# io-board.net
KiCad netlist of a schematic drawn in EAGLE
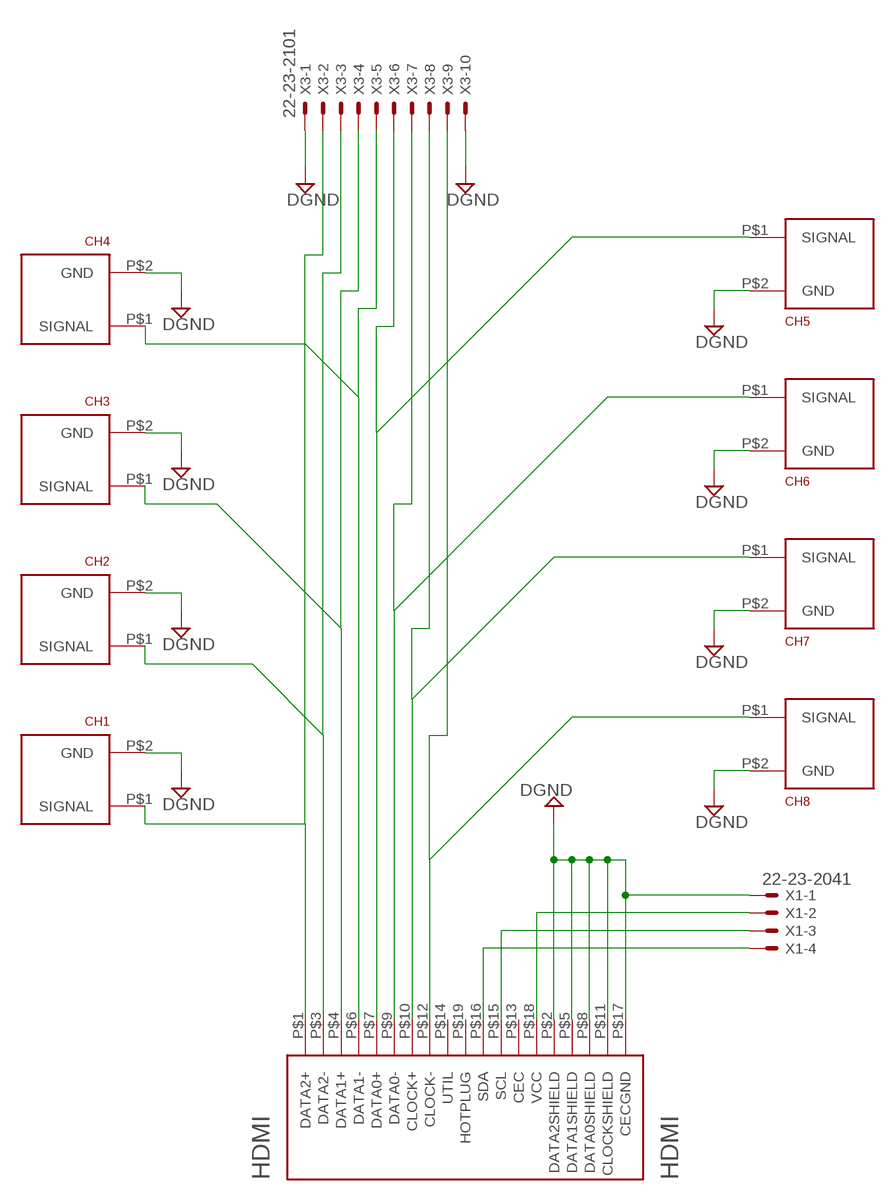
[diagram p0: schematic, sheet 1]

(export (version "E")
  (design (tool "Eeschema 10.0.6"))
  (components
    (comp (ref "CH1")
      (value "BNC_VERTICAL")
      (footprint "eagle-import:BNC_VERTICAL")
      (libsource (lib "eagle-import") (part "BNC_VERTICAL"))
    )
    (comp (ref "CH2")
      (value "BNC_VERTICAL")
      (footprint "eagle-import:BNC_VERTICAL")
      (libsource (lib "eagle-import") (part "BNC_VERTICAL"))
    )
    (comp (ref "CH3")
      (value "BNC_VERTICAL")
      (footprint "eagle-import:BNC_VERTICAL")
      (libsource (lib "eagle-import") (part "BNC_VERTICAL"))
    )
    (comp (ref "CH4")
      (value "BNC_VERTICAL")
      (footprint "eagle-import:BNC_VERTICAL")
      (libsource (lib "eagle-import") (part "BNC_VERTICAL"))
    )
    (comp (ref "CH5")
      (value "BNC_VERTICAL")
      (footprint "eagle-import:BNC_VERTICAL")
      (libsource (lib "eagle-import") (part "BNC_VERTICAL"))
    )
    (comp (ref "CH6")
      (value "BNC_VERTICAL")
      (footprint "eagle-import:BNC_VERTICAL")
      (libsource (lib "eagle-import") (part "BNC_VERTICAL"))
    )
    (comp (ref "CH7")
      (value "BNC_VERTICAL")
      (footprint "eagle-import:BNC_VERTICAL")
      (libsource (lib "eagle-import") (part "BNC_VERTICAL"))
    )
    (comp (ref "CH8")
      (value "BNC_VERTICAL")
      (footprint "eagle-import:BNC_VERTICAL")
      (libsource (lib "eagle-import") (part "BNC_VERTICAL"))
    )
    (comp (ref "HDMI")
      (value "HDMI")
      (footprint "eagle-import:HDMI_A")
      (libsource (lib "eagle-import") (part "HDMI"))
    )
    (comp (ref "X1")
      (value "22-23-2041")
      (footprint "eagle-import:22-23-2041")
      (fields (field (name "MF") "MOLEX"))
      (libsource (lib "eagle-import") (part "22-23-2041"))
    )
    (comp (ref "X3")
      (value "22-23-2101")
      (footprint "eagle-import:22-23-2101")
      (fields (field (name "MF") "MOLEX"))
      (libsource (lib "eagle-import") (part "22-23-2101"))
    )
  )
  (nets
    (net (code "1") (name "DGND") (class "Default")
      (node (ref "CH1") (pin "P$2") (pinfunction "GND_P$2") (pintype "bidirectional"))
      (node (ref "CH2") (pin "P$2") (pinfunction "GND_P$2") (pintype "bidirectional"))
      (node (ref "CH3") (pin "P$2") (pinfunction "GND_P$2") (pintype "bidirectional"))
      (node (ref "CH4") (pin "P$2") (pinfunction "GND_P$2") (pintype "bidirectional"))
      (node (ref "CH5") (pin "P$2") (pinfunction "GND_P$2") (pintype "bidirectional"))
      (node (ref "CH6") (pin "P$2") (pinfunction "GND_P$2") (pintype "bidirectional"))
      (node (ref "CH7") (pin "P$2") (pinfunction "GND_P$2") (pintype "bidirectional"))
      (node (ref "CH8") (pin "P$2") (pinfunction "GND_P$2") (pintype "bidirectional"))
      (node (ref "HDMI") (pin "P$11") (pinfunction "CLOCKSHIELD_P$11") (pintype "bidirectional"))
      (node (ref "HDMI") (pin "P$17") (pinfunction "CECGND_P$17") (pintype "bidirectional"))
      (node (ref "HDMI") (pin "P$2") (pinfunction "DATA2SHIELD_P$2") (pintype "bidirectional"))
      (node (ref "HDMI") (pin "P$5") (pinfunction "DATA1SHIELD_P$5") (pintype "bidirectional"))
      (node (ref "HDMI") (pin "P$8") (pinfunction "DATA0SHIELD_P$8") (pintype "bidirectional"))
      (node (ref "X1") (pin "1") (pinfunction "S_1") (pintype "passive"))
      (node (ref "X3") (pin "1") (pinfunction "S_1") (pintype "passive"))
      (node (ref "X3") (pin "10") (pinfunction "S_10") (pintype "passive"))
    )
    (net (code "2") (name "Net-(CH1-SIGNAL)") (class "Default")
      (node (ref "CH1") (pin "P$1") (pinfunction "SIGNAL_P$1") (pintype "bidirectional"))
      (node (ref "HDMI") (pin "P$1") (pinfunction "DATA2+_P$1") (pintype "bidirectional"))
      (node (ref "X3") (pin "2") (pinfunction "S_2") (pintype "passive"))
    )
    (net (code "3") (name "Net-(CH2-SIGNAL)") (class "Default")
      (node (ref "CH2") (pin "P$1") (pinfunction "SIGNAL_P$1") (pintype "bidirectional"))
      (node (ref "HDMI") (pin "P$3") (pinfunction "DATA2-_P$3") (pintype "bidirectional"))
      (node (ref "X3") (pin "3") (pinfunction "S_3") (pintype "passive"))
    )
    (net (code "4") (name "Net-(CH3-SIGNAL)") (class "Default")
      (node (ref "CH3") (pin "P$1") (pinfunction "SIGNAL_P$1") (pintype "bidirectional"))
      (node (ref "HDMI") (pin "P$4") (pinfunction "DATA1+_P$4") (pintype "bidirectional"))
      (node (ref "X3") (pin "4") (pinfunction "S_4") (pintype "passive"))
    )
    (net (code "5") (name "Net-(CH4-SIGNAL)") (class "Default")
      (node (ref "CH4") (pin "P$1") (pinfunction "SIGNAL_P$1") (pintype "bidirectional"))
      (node (ref "HDMI") (pin "P$6") (pinfunction "DATA1-_P$6") (pintype "bidirectional"))
      (node (ref "X3") (pin "5") (pinfunction "S_5") (pintype "passive"))
    )
    (net (code "6") (name "Net-(CH5-SIGNAL)") (class "Default")
      (node (ref "CH5") (pin "P$1") (pinfunction "SIGNAL_P$1") (pintype "bidirectional"))
      (node (ref "HDMI") (pin "P$7") (pinfunction "DATA0+_P$7") (pintype "bidirectional"))
      (node (ref "X3") (pin "6") (pinfunction "S_6") (pintype "passive"))
    )
    (net (code "7") (name "Net-(CH6-SIGNAL)") (class "Default")
      (node (ref "CH6") (pin "P$1") (pinfunction "SIGNAL_P$1") (pintype "bidirectional"))
      (node (ref "HDMI") (pin "P$9") (pinfunction "DATA0-_P$9") (pintype "bidirectional"))
      (node (ref "X3") (pin "7") (pinfunction "S_7") (pintype "passive"))
    )
    (net (code "8") (name "Net-(CH7-SIGNAL)") (class "Default")
      (node (ref "CH7") (pin "P$1") (pinfunction "SIGNAL_P$1") (pintype "bidirectional"))
      (node (ref "HDMI") (pin "P$10") (pinfunction "CLOCK+_P$10") (pintype "bidirectional"))
      (node (ref "X3") (pin "8") (pinfunction "S_8") (pintype "passive"))
    )
    (net (code "9") (name "Net-(CH8-SIGNAL)") (class "Default")
      (node (ref "CH8") (pin "P$1") (pinfunction "SIGNAL_P$1") (pintype "bidirectional"))
      (node (ref "HDMI") (pin "P$12") (pinfunction "CLOCK-_P$12") (pintype "bidirectional"))
      (node (ref "X3") (pin "9") (pinfunction "S_9") (pintype "passive"))
    )
    (net (code "10") (name "Net-(HDMI-SCL)") (class "Default")
      (node (ref "HDMI") (pin "P$15") (pinfunction "SCL_P$15") (pintype "bidirectional"))
      (node (ref "X1") (pin "3") (pinfunction "S_3") (pintype "passive"))
    )
    (net (code "11") (name "Net-(HDMI-SDA)") (class "Default")
      (node (ref "HDMI") (pin "P$16") (pinfunction "SDA_P$16") (pintype "bidirectional"))
      (node (ref "X1") (pin "4") (pinfunction "S_4") (pintype "passive"))
    )
    (net (code "12") (name "Net-(HDMI-VCC)") (class "Default")
      (node (ref "HDMI") (pin "P$18") (pinfunction "VCC_P$18") (pintype "bidirectional"))
      (node (ref "X1") (pin "2") (pinfunction "S_2") (pintype "passive"))
    )
    (net (code "13") (name "unconnected-(HDMI-CEC-PadP$13)") (class "Default")
      (node (ref "HDMI") (pin "P$13") (pinfunction "CEC_P$13") (pintype "bidirectional"))
    )
    (net (code "14") (name "unconnected-(HDMI-HOTPLUG-PadP$19)") (class "Default")
      (node (ref "HDMI") (pin "P$19") (pinfunction "HOTPLUG_P$19") (pintype "bidirectional"))
    )
    (net (code "15") (name "unconnected-(HDMI-UTIL-PadP$14)") (class "Default")
      (node (ref "HDMI") (pin "P$14") (pinfunction "UTIL_P$14") (pintype "bidirectional"))
    )
  )
)
